# MD201x_2019-02-01.net
KiCad netlist of a schematic drawn in EAGLE
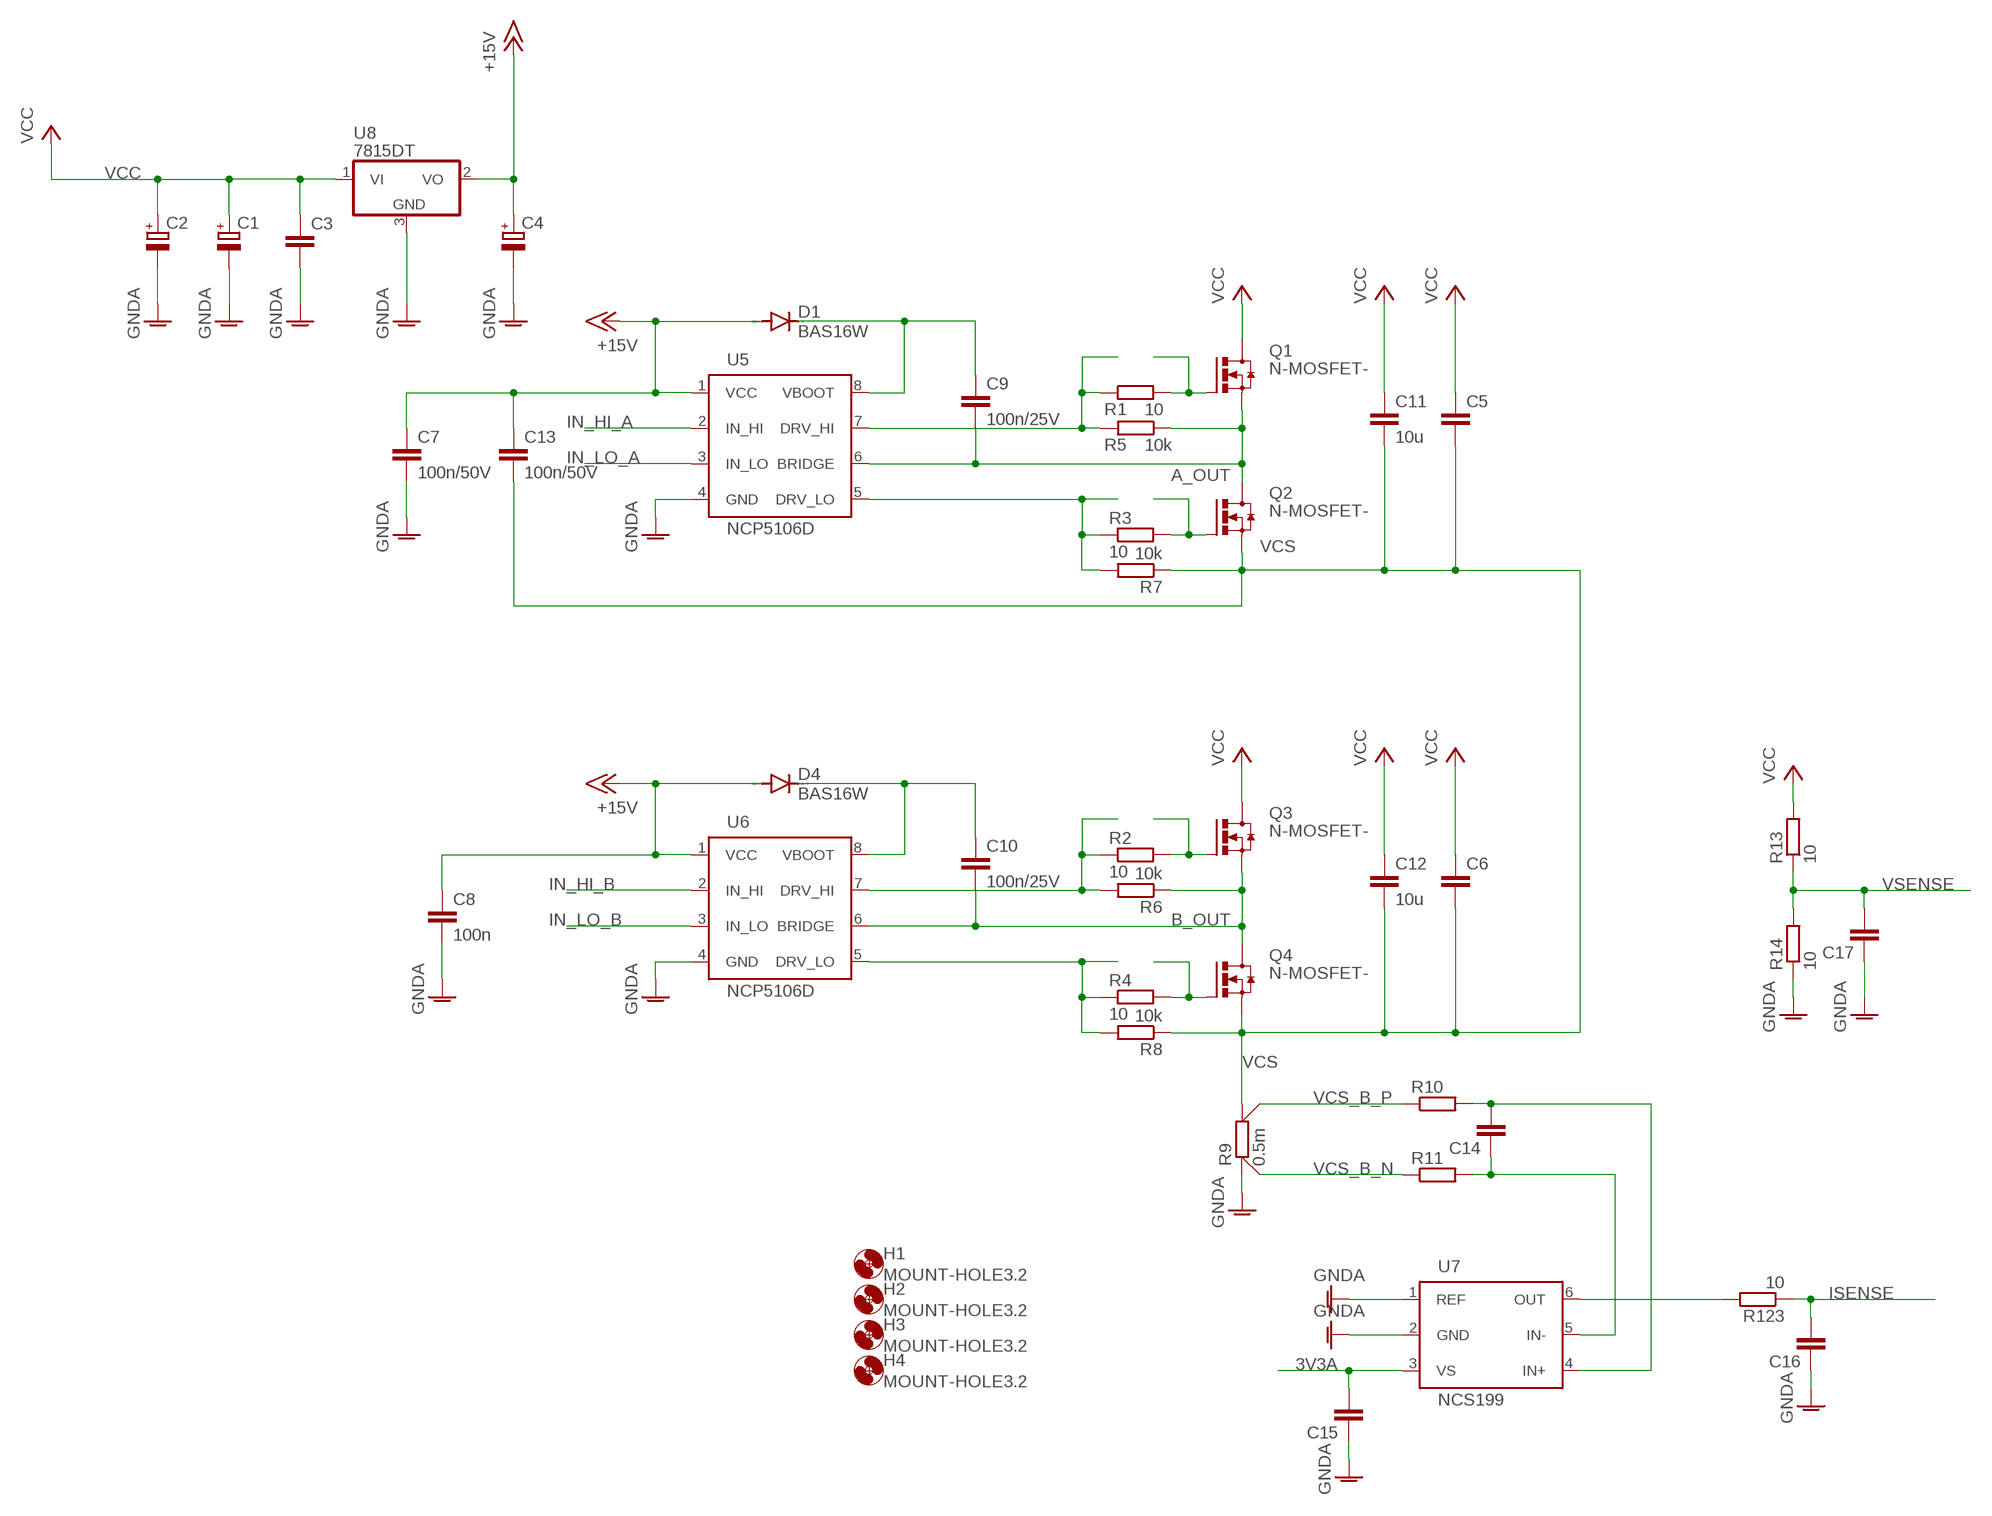
[diagram p0: schematic, sheet 1]
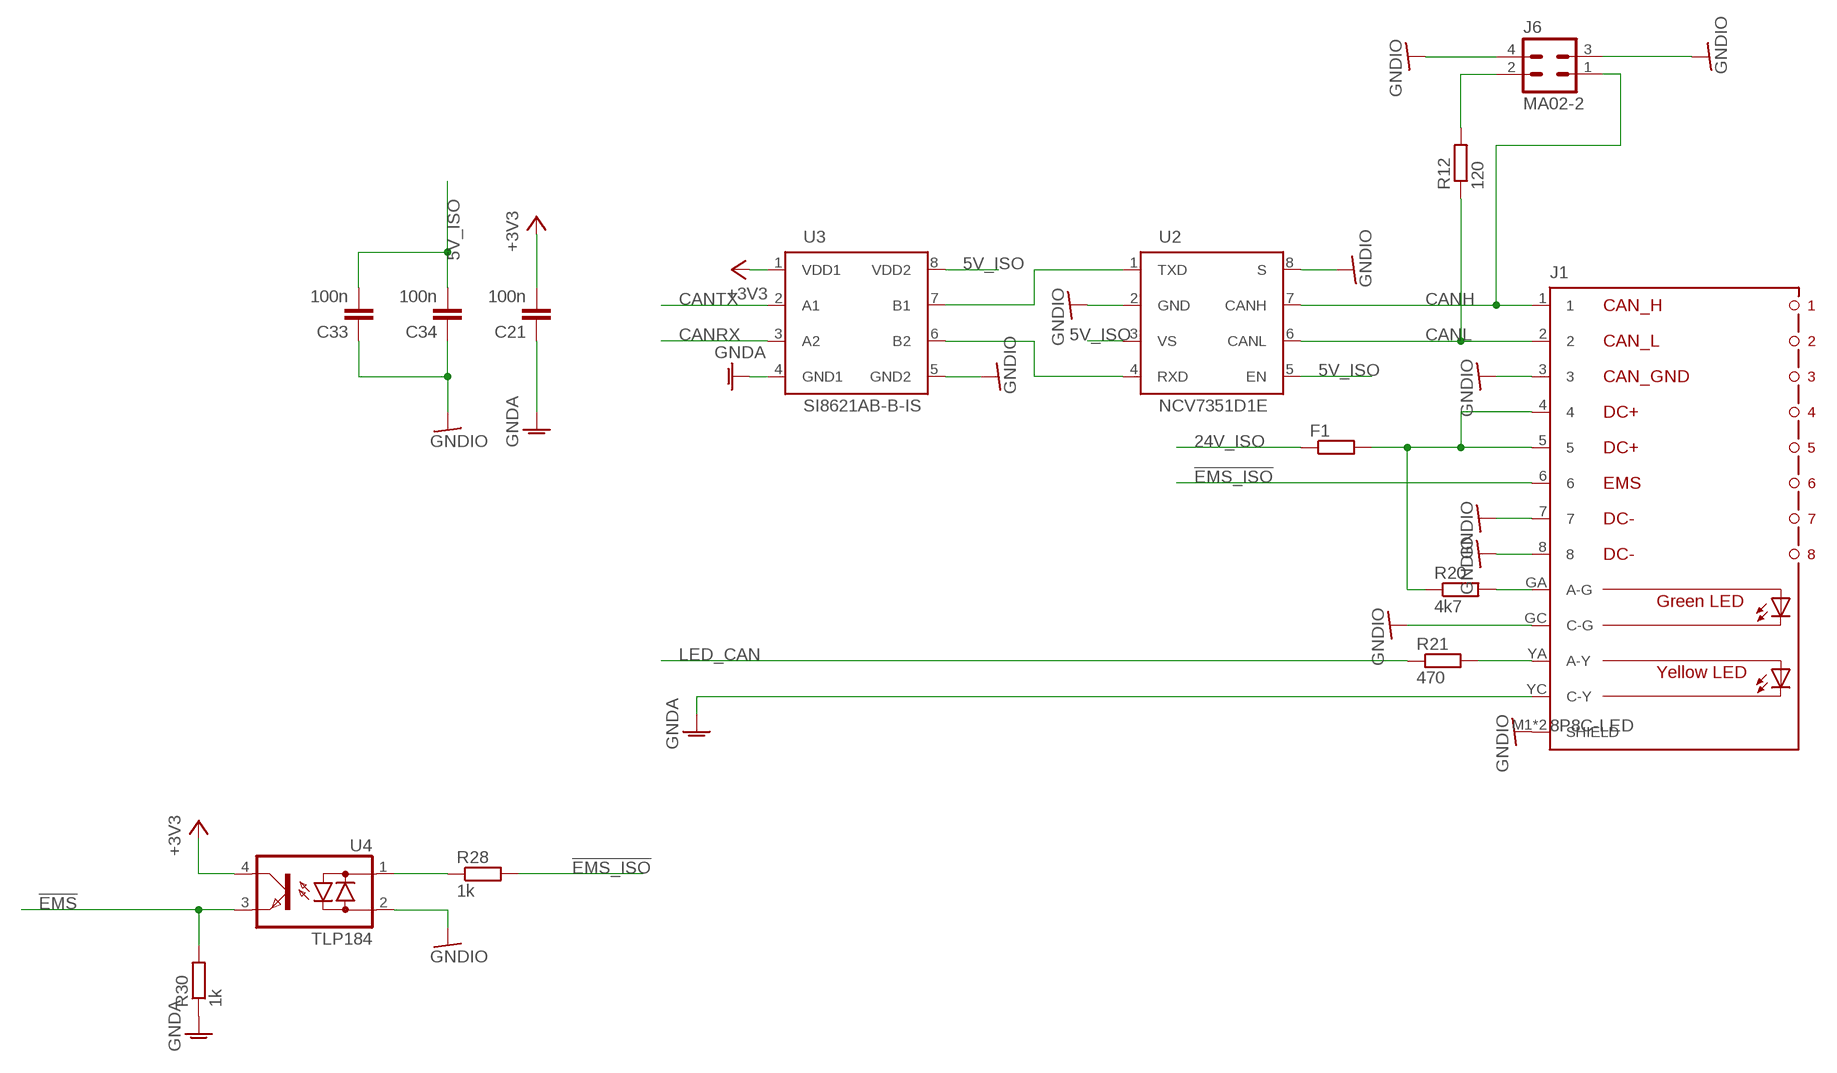
[diagram p1: schematic, sheet 2]
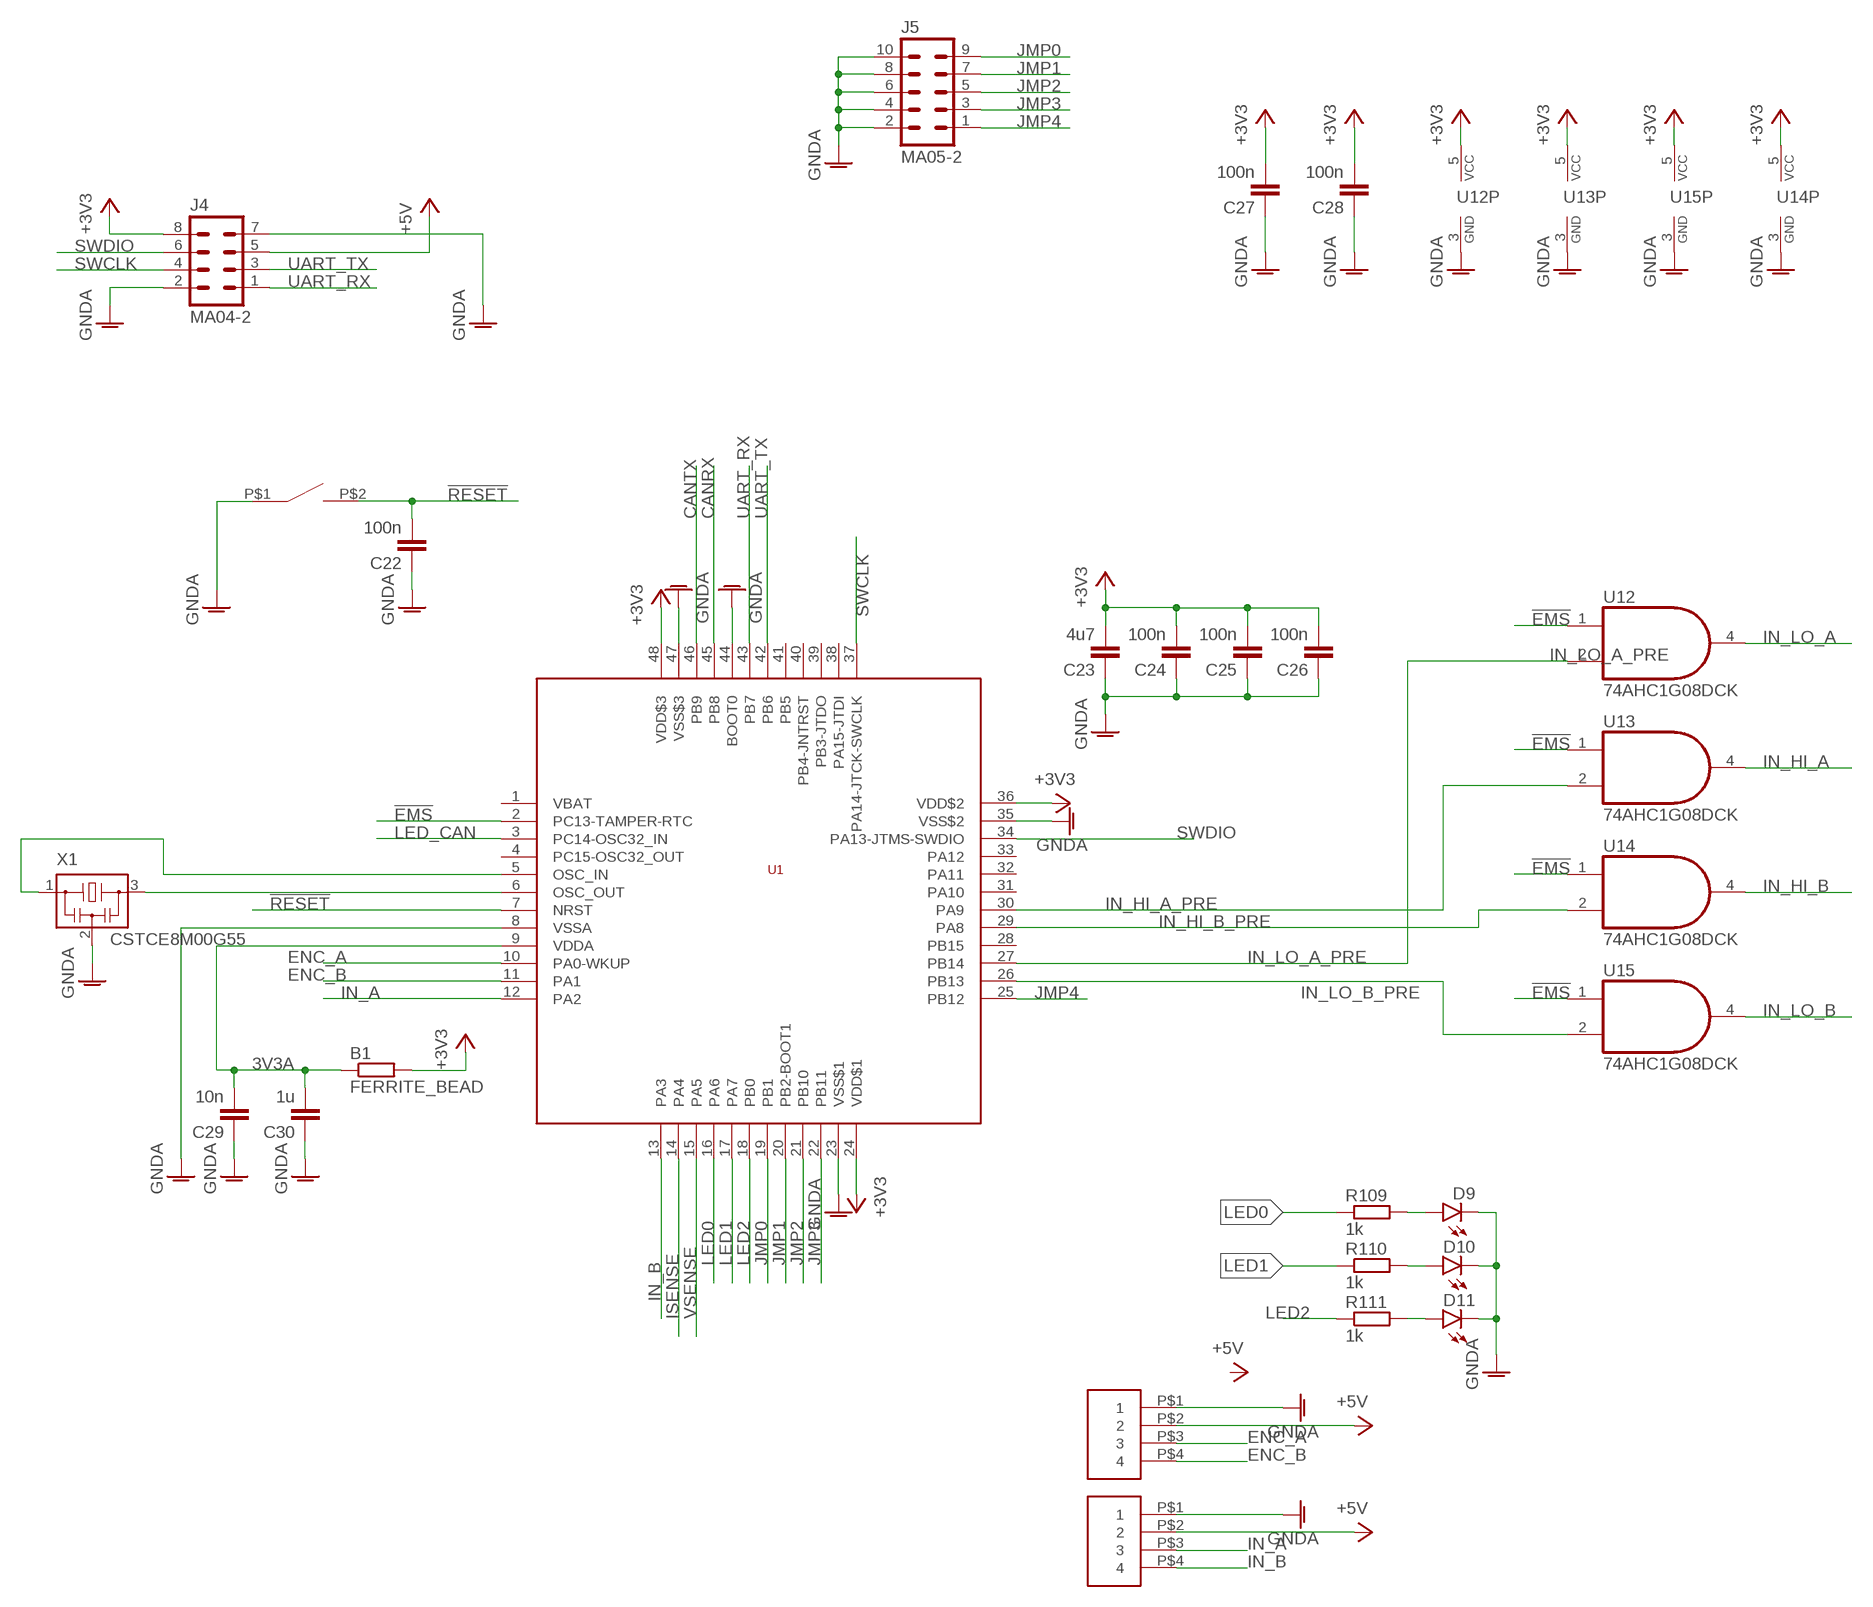
[diagram p2: schematic, sheet 3]
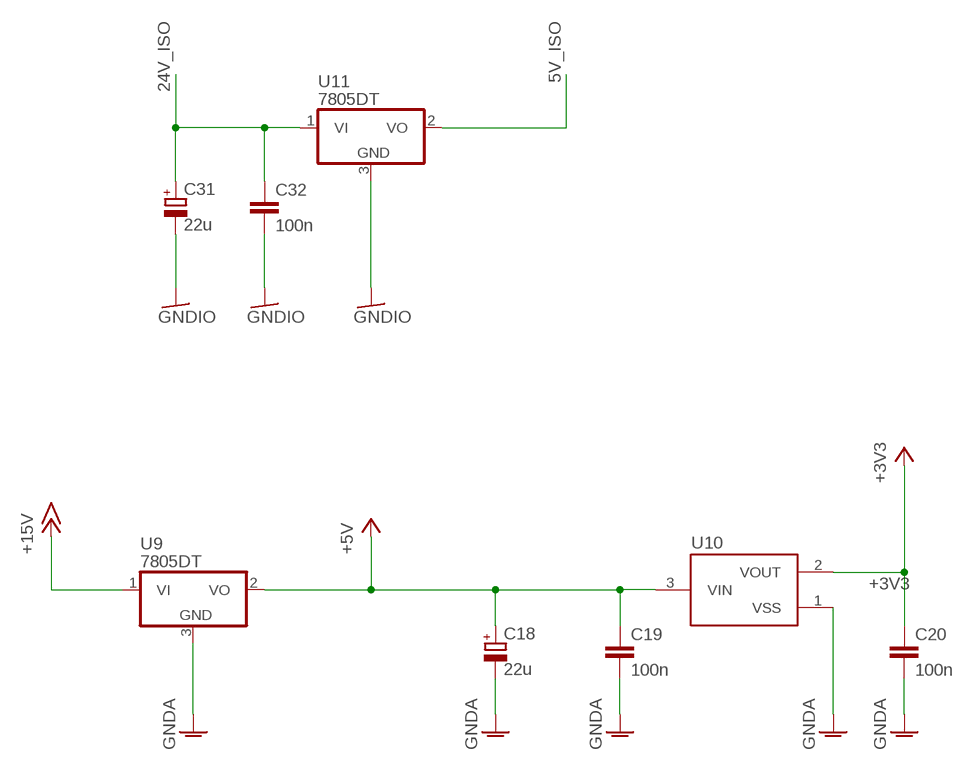
[diagram p3: schematic, sheet 4]

(export (version "E")
  (design (tool "Eeschema 10.0.6"))
  (components
    (comp (ref "C18")
      (value "22u")
      (footprint "eagle-import:E2,5-5")
      (libsource (lib "eagle-import") (part "CPOL-EUE2.5-5"))
    )
    (comp (ref "C19")
      (value "100n")
      (footprint "eagle-import:C0603")
      (libsource (lib "eagle-import") (part "C-EUC0603"))
    )
    (comp (ref "C20")
      (value "100n")
      (footprint "eagle-import:C0603")
      (libsource (lib "eagle-import") (part "C-EUC0603"))
    )
    (comp (ref "C31")
      (value "22u")
      (footprint "eagle-import:E2,5-5")
      (libsource (lib "eagle-import") (part "CPOL-EUE2.5-5"))
    )
    (comp (ref "C32")
      (value "100n")
      (footprint "eagle-import:C0603")
      (libsource (lib "eagle-import") (part "C-EUC0603"))
    )
    (comp (ref "U9")
      (value "7805DT")
      (footprint "eagle-import:TO252")
      (libsource (lib "eagle-import") (part "78DT05"))
    )
    (comp (ref "U10")
      (value "XC6206")
      (footprint "eagle-import:SOT95P240X110-3")
      (libsource (lib "eagle-import") (part "XC6206"))
    )
    (comp (ref "U11")
      (value "7805DT")
      (footprint "eagle-import:TO252")
      (libsource (lib "eagle-import") (part "78DT05"))
    )
    (comp (ref "C1")
      (value "CPOL-EUE5-10.5")
      (footprint "eagle-import:E5-10,5")
      (libsource (lib "eagle-import") (part "CPOL-EUE5-10.5"))
    )
    (comp (ref "C2")
      (value "CPOL-EUE5-10.5")
      (footprint "eagle-import:E5-10,5")
      (libsource (lib "eagle-import") (part "CPOL-EUE5-10.5"))
    )
    (comp (ref "C3")
      (value "C-EUC0603")
      (footprint "eagle-import:C0603")
      (libsource (lib "eagle-import") (part "C-EUC0603"))
    )
    (comp (ref "C4")
      (value "CPOL-EUE2.5-5")
      (footprint "eagle-import:E2,5-5")
      (libsource (lib "eagle-import") (part "CPOL-EUE2.5-5"))
    )
    (comp (ref "C5")
      (value "C-EUC0603")
      (footprint "eagle-import:C0603")
      (libsource (lib "eagle-import") (part "C-EUC0603"))
    )
    (comp (ref "C6")
      (value "C-EUC0603")
      (footprint "eagle-import:C0603")
      (libsource (lib "eagle-import") (part "C-EUC0603"))
    )
    (comp (ref "C7")
      (value "100n/50V")
      (footprint "eagle-import:C0603")
      (libsource (lib "eagle-import") (part "C-EUC0603"))
    )
    (comp (ref "C8")
      (value "100n")
      (footprint "eagle-import:C0603")
      (libsource (lib "eagle-import") (part "C-EUC0603"))
    )
    (comp (ref "C9")
      (value "100n/25V")
      (footprint "eagle-import:C0603")
      (libsource (lib "eagle-import") (part "C-EUC0603"))
    )
    (comp (ref "C10")
      (value "100n/25V")
      (footprint "eagle-import:C0603")
      (libsource (lib "eagle-import") (part "C-EUC0603"))
    )
    (comp (ref "C11")
      (value "10u")
      (footprint "eagle-import:C1210")
      (libsource (lib "eagle-import") (part "C-EUC1210"))
    )
    (comp (ref "C12")
      (value "10u")
      (footprint "eagle-import:C1210")
      (libsource (lib "eagle-import") (part "C-EUC1210"))
    )
    (comp (ref "C13")
      (value "100n/50V")
      (footprint "eagle-import:C0603")
      (libsource (lib "eagle-import") (part "C-EUC0603"))
    )
    (comp (ref "C14")
      (value "C-EUC0603")
      (footprint "eagle-import:C0603")
      (libsource (lib "eagle-import") (part "rcl_334_C-EUC0603"))
    )
    (comp (ref "C15")
      (value "C-EUC0603")
      (footprint "eagle-import:C0603")
      (libsource (lib "eagle-import") (part "rcl_334_C-EUC0603"))
    )
    (comp (ref "C16")
      (value "C-EUC0603")
      (footprint "eagle-import:C0603")
      (libsource (lib "eagle-import") (part "rcl_334_C-EUC0603"))
    )
    (comp (ref "C17")
      (value "C-EUC0603")
      (footprint "eagle-import:C0603")
      (libsource (lib "eagle-import") (part "rcl_334_C-EUC0603"))
    )
    (comp (ref "D1")
      (value "BAS16W")
      (footprint "eagle-import:SOD323-R")
      (libsource (lib "eagle-import") (part "DIODE-SOD323-R"))
    )
    (comp (ref "D4")
      (value "BAS16W")
      (footprint "eagle-import:SOD323-R")
      (libsource (lib "eagle-import") (part "DIODE-SOD323-R"))
    )
    (comp (ref "H1")
      (value "MOUNT-HOLE3.2")
      (footprint "eagle-import:3,2")
      (libsource (lib "eagle-import") (part "MOUNT-HOLE3.2"))
    )
    (comp (ref "H2")
      (value "MOUNT-HOLE3.2")
      (footprint "eagle-import:3,2")
      (libsource (lib "eagle-import") (part "MOUNT-HOLE3.2"))
    )
    (comp (ref "H3")
      (value "MOUNT-HOLE3.2")
      (footprint "eagle-import:3,2")
      (libsource (lib "eagle-import") (part "MOUNT-HOLE3.2"))
    )
    (comp (ref "H4")
      (value "MOUNT-HOLE3.2")
      (footprint "eagle-import:3,2")
      (libsource (lib "eagle-import") (part "MOUNT-HOLE3.2"))
    )
    (comp (ref "Q1")
      (value "N-MOSFET-")
      (footprint "eagle-import:SOT669")
      (libsource (lib "eagle-import") (part "N-MOSFET-"))
    )
    (comp (ref "Q2")
      (value "N-MOSFET-")
      (footprint "eagle-import:SOT669")
      (libsource (lib "eagle-import") (part "N-MOSFET-"))
    )
    (comp (ref "Q3")
      (value "N-MOSFET-")
      (footprint "eagle-import:SOT669")
      (libsource (lib "eagle-import") (part "N-MOSFET-"))
    )
    (comp (ref "Q4")
      (value "N-MOSFET-")
      (footprint "eagle-import:SOT669")
      (libsource (lib "eagle-import") (part "N-MOSFET-"))
    )
    (comp (ref "R1")
      (value "10")
      (footprint "eagle-import:R0603")
      (libsource (lib "eagle-import") (part "R-EU_R0603"))
    )
    (comp (ref "R2")
      (value "10")
      (footprint "eagle-import:R0603")
      (libsource (lib "eagle-import") (part "R-EU_R0603"))
    )
    (comp (ref "R3")
      (value "10")
      (footprint "eagle-import:R0603")
      (libsource (lib "eagle-import") (part "R-EU_R0603"))
    )
    (comp (ref "R4")
      (value "10")
      (footprint "eagle-import:R0603")
      (libsource (lib "eagle-import") (part "R-EU_R0603"))
    )
    (comp (ref "R5")
      (value "10k")
      (footprint "eagle-import:R0603")
      (libsource (lib "eagle-import") (part "R-EU_R0603"))
    )
    (comp (ref "R6")
      (value "10k")
      (footprint "eagle-import:R0603")
      (libsource (lib "eagle-import") (part "R-EU_R0603"))
    )
    (comp (ref "R7")
      (value "10k")
      (footprint "eagle-import:R0603")
      (libsource (lib "eagle-import") (part "R-EU_R0603"))
    )
    (comp (ref "R8")
      (value "10k")
      (footprint "eagle-import:R0603")
      (libsource (lib "eagle-import") (part "R-EU_R0603"))
    )
    (comp (ref "R9")
      (value "0.5m")
      (footprint "eagle-import:CSS2H-2512")
      (libsource (lib "eagle-import") (part "CSS2H-2512"))
    )
    (comp (ref "R10")
      (value "R-EU_R0603")
      (footprint "eagle-import:R0603")
      (libsource (lib "eagle-import") (part "rcl_334_R-EU_R0603"))
    )
    (comp (ref "R11")
      (value "R-EU_R0603")
      (footprint "eagle-import:R0603")
      (libsource (lib "eagle-import") (part "rcl_334_R-EU_R0603"))
    )
    (comp (ref "R13")
      (value "10")
      (footprint "eagle-import:R0603")
      (libsource (lib "eagle-import") (part "R-EU_R0603"))
    )
    (comp (ref "R14")
      (value "10")
      (footprint "eagle-import:R0603")
      (libsource (lib "eagle-import") (part "R-EU_R0603"))
    )
    (comp (ref "R123")
      (value "10")
      (footprint "eagle-import:R0603")
      (libsource (lib "eagle-import") (part "R-EU_R0603"))
    )
    (comp (ref "U5")
      (value "NCP5106D")
      (footprint "eagle-import:SOIC127P600X175-8")
      (libsource (lib "eagle-import") (part "NCP5106D"))
    )
    (comp (ref "U6")
      (value "NCP5106D")
      (footprint "eagle-import:SOIC127P600X175-8")
      (libsource (lib "eagle-import") (part "NCP5106D"))
    )
    (comp (ref "U7")
      (value "NCS199")
      (footprint "eagle-import:SOT65P210X110-6")
      (libsource (lib "eagle-import") (part "NCS199"))
    )
    (comp (ref "U8")
      (value "7815DT")
      (footprint "eagle-import:TO252")
      (libsource (lib "eagle-import") (part "78DT15"))
    )
    (comp (ref "B1")
      (value "FERRITE_BEAD")
      (footprint "eagle-import:R0603")
      (libsource (lib "eagle-import") (part "R-EU_R0603"))
    )
    (comp (ref "C22")
      (value "100n")
      (footprint "eagle-import:C0603")
      (libsource (lib "eagle-import") (part "C-EUC0603"))
    )
    (comp (ref "C23")
      (value "4u7")
      (footprint "eagle-import:C0805")
      (libsource (lib "eagle-import") (part "C-EUC0805"))
    )
    (comp (ref "C24")
      (value "100n")
      (footprint "eagle-import:C0603")
      (libsource (lib "eagle-import") (part "C-EUC0603"))
    )
    (comp (ref "C25")
      (value "100n")
      (footprint "eagle-import:C0603")
      (libsource (lib "eagle-import") (part "C-EUC0603"))
    )
    (comp (ref "C26")
      (value "100n")
      (footprint "eagle-import:C0603")
      (libsource (lib "eagle-import") (part "C-EUC0603"))
    )
    (comp (ref "C27")
      (value "100n")
      (footprint "eagle-import:C0603")
      (libsource (lib "eagle-import") (part "C-EUC0603"))
    )
    (comp (ref "C28")
      (value "100n")
      (footprint "eagle-import:C0603")
      (libsource (lib "eagle-import") (part "C-EUC0603"))
    )
    (comp (ref "C29")
      (value "10n")
      (footprint "eagle-import:C0603")
      (libsource (lib "eagle-import") (part "C-EUC0603"))
    )
    (comp (ref "C30")
      (value "1u")
      (footprint "eagle-import:C0603")
      (libsource (lib "eagle-import") (part "C-EUC0603"))
    )
    (comp (ref "D9")
      (value "LEDCHIPLED_0805")
      (footprint "eagle-import:CHIPLED_0805")
      (libsource (lib "eagle-import") (part "LEDCHIPLED_0805"))
    )
    (comp (ref "D10")
      (value "LEDCHIPLED_0805")
      (footprint "eagle-import:CHIPLED_0805")
      (libsource (lib "eagle-import") (part "LEDCHIPLED_0805"))
    )
    (comp (ref "D11")
      (value "LEDCHIPLED_0805")
      (footprint "eagle-import:CHIPLED_0805")
      (libsource (lib "eagle-import") (part "LEDCHIPLED_0805"))
    )
    (comp (ref "J2")
      (value "XH-4-SIDE")
      (footprint "eagle-import:CON-XH-4-SIDE")
      (libsource (lib "eagle-import") (part "XH-4-SIDE"))
    )
    (comp (ref "J3")
      (value "XH-4-SIDE")
      (footprint "eagle-import:CON-XH-4-SIDE")
      (libsource (lib "eagle-import") (part "XH-4-SIDE"))
    )
    (comp (ref "J4")
      (value "MA04-2")
      (footprint "eagle-import:MA04-2W")
      (libsource (lib "eagle-import") (part "MA04-2"))
    )
    (comp (ref "J5")
      (value "MA05-2")
      (footprint "eagle-import:MA05-2W")
      (libsource (lib "eagle-import") (part "MA05-2"))
    )
    (comp (ref "R109")
      (value "1k")
      (footprint "eagle-import:R0603")
      (libsource (lib "eagle-import") (part "R-EU_R0603"))
    )
    (comp (ref "R110")
      (value "1k")
      (footprint "eagle-import:R0603")
      (libsource (lib "eagle-import") (part "R-EU_R0603"))
    )
    (comp (ref "R111")
      (value "1k")
      (footprint "eagle-import:R0603")
      (libsource (lib "eagle-import") (part "R-EU_R0603"))
    )
    (comp (ref "S1")
      (value "SWITCH_TACTILETOP")
      (footprint "eagle-import:SWITCH_TACTILE_3X6")
      (libsource (lib "eagle-import") (part "SWITCH_TACTILETOP"))
    )
    (comp (ref "U1")
      (value "STM32F103C8")
      (footprint "eagle-import:LQFP48")
      (libsource (lib "eagle-import") (part "STM32F103C8"))
    )
    (comp (ref "U12")
      (value "74AHC1G08DCK")
      (footprint "eagle-import:SC70-5")
      (libsource (lib "eagle-import") (part "741G08DCKAHC"))
    )
    (comp (ref "U13")
      (value "74AHC1G08DCK")
      (footprint "eagle-import:SC70-5")
      (libsource (lib "eagle-import") (part "741G08DCKAHC"))
    )
    (comp (ref "U14")
      (value "74AHC1G08DCK")
      (footprint "eagle-import:SC70-5")
      (libsource (lib "eagle-import") (part "741G08DCKAHC"))
    )
    (comp (ref "U15")
      (value "74AHC1G08DCK")
      (footprint "eagle-import:SC70-5")
      (libsource (lib "eagle-import") (part "741G08DCKAHC"))
    )
    (comp (ref "X1")
      (value "CSTCE8M00G55")
      (footprint "eagle-import:CSTCE8M00G55")
      (libsource (lib "eagle-import") (part "CSTCE8M00G55"))
    )
    (comp (ref "C21")
      (value "100n")
      (footprint "eagle-import:C0603")
      (libsource (lib "eagle-import") (part "C-EUC0603"))
    )
    (comp (ref "C33")
      (value "100n")
      (footprint "eagle-import:C0805")
      (libsource (lib "eagle-import") (part "C-EUC0805"))
    )
    (comp (ref "C34")
      (value "100n")
      (footprint "eagle-import:C0603")
      (libsource (lib "eagle-import") (part "C-EUC0603"))
    )
    (comp (ref "F1")
      (value "R-EU_R1206")
      (footprint "eagle-import:R1206")
      (libsource (lib "eagle-import") (part "rcl_334_R-EU_R1206"))
    )
    (comp (ref "J1")
      (value "8P8C-LED")
      (footprint "eagle-import:8P8C-LED")
      (libsource (lib "eagle-import") (part "8P8C-LED"))
    )
    (comp (ref "J6")
      (value "MA02-2")
      (footprint "eagle-import:MA02-2W")
      (libsource (lib "eagle-import") (part "MA02-2"))
    )
    (comp (ref "R12")
      (value "120")
      (footprint "eagle-import:R0603")
      (libsource (lib "eagle-import") (part "rcl_334_R-EU_R0603"))
    )
    (comp (ref "R20")
      (value "4k7")
      (footprint "eagle-import:R0603")
      (libsource (lib "eagle-import") (part "rcl_334_R-EU_R0603"))
    )
    (comp (ref "R21")
      (value "470")
      (footprint "eagle-import:R0603")
      (libsource (lib "eagle-import") (part "rcl_334_R-EU_R0603"))
    )
    (comp (ref "R28")
      (value "1k")
      (footprint "eagle-import:R0603")
      (libsource (lib "eagle-import") (part "rcl_334_R-EU_R0603"))
    )
    (comp (ref "R30")
      (value "1k")
      (footprint "eagle-import:R0603")
      (libsource (lib "eagle-import") (part "rcl_334_R-EU_R0603"))
    )
    (comp (ref "U2")
      (value "NCV7351D1E")
      (footprint "eagle-import:SO08")
      (libsource (lib "eagle-import") (part "NCV7351D1E"))
    )
    (comp (ref "U3")
      (value "SI8621AB-B-IS")
      (footprint "eagle-import:SO08")
      (libsource (lib "eagle-import") (part "SI8621AB-B-IS"))
    )
    (comp (ref "U4")
      (value "TLP184")
      (footprint "eagle-import:11-4M1S")
      (libsource (lib "eagle-import") (part "TLP184"))
    )
  )
  (nets
    (net (code "1") (name "+3V3") (class "Default")
      (node (ref "B1") (pin "2") (pinfunction "2_2") (pintype "passive"))
      (node (ref "C20") (pin "1") (pinfunction "1_1") (pintype "passive"))
      (node (ref "C21") (pin "2") (pinfunction "2_2") (pintype "passive"))
      (node (ref "C23") (pin "2") (pinfunction "2_2") (pintype "passive"))
      (node (ref "C24") (pin "2") (pinfunction "2_2") (pintype "passive"))
      (node (ref "C25") (pin "2") (pinfunction "2_2") (pintype "passive"))
      (node (ref "C26") (pin "2") (pinfunction "2_2") (pintype "passive"))
      (node (ref "C27") (pin "2") (pinfunction "2_2") (pintype "passive"))
      (node (ref "C28") (pin "2") (pinfunction "2_2") (pintype "passive"))
      (node (ref "J4") (pin "8") (pinfunction "8_8") (pintype "passive"))
      (node (ref "U1") (pin "24") (pinfunction "VDD$1_24") (pintype "passive"))
      (node (ref "U1") (pin "36") (pinfunction "VDD$2_36") (pintype "passive"))
      (node (ref "U1") (pin "48") (pinfunction "VDD$3_48") (pintype "passive"))
      (node (ref "U10") (pin "2") (pinfunction "VOUT_2") (pintype "bidirectional"))
      (node (ref "U12") (pin "5") (pinfunction "VCC_5") (pintype "power_in"))
      (node (ref "U13") (pin "5") (pinfunction "VCC_5") (pintype "power_in"))
      (node (ref "U14") (pin "5") (pinfunction "VCC_5") (pintype "power_in"))
      (node (ref "U15") (pin "5") (pinfunction "VCC_5") (pintype "power_in"))
      (node (ref "U3") (pin "1") (pinfunction "VDD1_1") (pintype "power_in"))
      (node (ref "U4") (pin "4") (pinfunction "C_4") (pintype "passive"))
    )
    (net (code "2") (name "+5V") (class "Default")
      (node (ref "C18") (pin "+") (pinfunction "+_+") (pintype "passive"))
      (node (ref "C19") (pin "1") (pinfunction "1_1") (pintype "passive"))
      (node (ref "J2") (pin "P$2") (pinfunction "2_P$2") (pintype "bidirectional"))
      (node (ref "J3") (pin "P$2") (pinfunction "2_P$2") (pintype "bidirectional"))
      (node (ref "J4") (pin "5") (pinfunction "5_5") (pintype "passive"))
      (node (ref "U10") (pin "3") (pinfunction "VIN_3") (pintype "bidirectional"))
      (node (ref "U9") (pin "2") (pinfunction "VO_2") (pintype "passive"))
    )
    (net (code "3") (name "+15V") (class "Default")
      (node (ref "C13") (pin "1") (pinfunction "1_1") (pintype "passive"))
      (node (ref "C4") (pin "+") (pinfunction "+_+") (pintype "passive"))
      (node (ref "C7") (pin "1") (pinfunction "1_1") (pintype "passive"))
      (node (ref "C8") (pin "1") (pinfunction "1_1") (pintype "passive"))
      (node (ref "D1") (pin "A") (pinfunction "A_A") (pintype "passive"))
      (node (ref "D4") (pin "A") (pinfunction "A_A") (pintype "passive"))
      (node (ref "U5") (pin "1") (pinfunction "VCC_1") (pintype "power_in"))
      (node (ref "U6") (pin "1") (pinfunction "VCC_1") (pintype "power_in"))
      (node (ref "U8") (pin "2") (pinfunction "VO_2") (pintype "passive"))
      (node (ref "U9") (pin "1") (pinfunction "VI_1") (pintype "input"))
    )
    (net (code "4") (name "3V3A") (class "Default")
      (node (ref "B1") (pin "1") (pinfunction "1_1") (pintype "passive"))
      (node (ref "C15") (pin "2") (pinfunction "2_2") (pintype "passive"))
      (node (ref "C29") (pin "2") (pinfunction "2_2") (pintype "passive"))
      (node (ref "C30") (pin "2") (pinfunction "2_2") (pintype "passive"))
      (node (ref "U1") (pin "9") (pinfunction "VDDA_9") (pintype "bidirectional"))
      (node (ref "U7") (pin "3") (pinfunction "VS_3") (pintype "power_in"))
    )
    (net (code "5") (name "5V_ISO") (class "Default")
      (node (ref "C33") (pin "2") (pinfunction "2_2") (pintype "passive"))
      (node (ref "C34") (pin "2") (pinfunction "2_2") (pintype "passive"))
      (node (ref "U11") (pin "2") (pinfunction "VO_2") (pintype "passive"))
      (node (ref "U2") (pin "3") (pinfunction "VS_3") (pintype "power_in"))
      (node (ref "U2") (pin "5") (pinfunction "EN_5") (pintype "input"))
      (node (ref "U3") (pin "8") (pinfunction "VDD2_8") (pintype "power_in"))
    )
    (net (code "6") (name "24V_ISO") (class "Default")
      (node (ref "C31") (pin "+") (pinfunction "+_+") (pintype "passive"))
      (node (ref "C32") (pin "1") (pinfunction "1_1") (pintype "passive"))
      (node (ref "F1") (pin "1") (pinfunction "1_1") (pintype "passive"))
      (node (ref "U11") (pin "1") (pinfunction "VI_1") (pintype "input"))
    )
    (net (code "7") (name "A_OUT") (class "Default")
      (node (ref "C9") (pin "2") (pinfunction "2_2") (pintype "passive"))
      (node (ref "Q1") (pin "1") (pinfunction "SOURCE_1") (pintype "passive"))
      (node (ref "Q1") (pin "2") (pinfunction "SOURCE_2") (pintype "passive"))
      (node (ref "Q1") (pin "3") (pinfunction "SOURCE_3") (pintype "passive"))
      (node (ref "Q2") (pin "5") (pinfunction "DRAIN_5") (pintype "passive"))
      (node (ref "R5") (pin "1") (pinfunction "1_1") (pintype "passive"))
      (node (ref "U5") (pin "6") (pinfunction "BRIDGE_6") (pintype "power_in"))
    )
    (net (code "8") (name "B_OUT") (class "Default")
      (node (ref "C10") (pin "2") (pinfunction "2_2") (pintype "passive"))
      (node (ref "Q3") (pin "1") (pinfunction "SOURCE_1") (pintype "passive"))
      (node (ref "Q3") (pin "2") (pinfunction "SOURCE_2") (pintype "passive"))
      (node (ref "Q3") (pin "3") (pinfunction "SOURCE_3") (pintype "passive"))
      (node (ref "Q4") (pin "5") (pinfunction "DRAIN_5") (pintype "passive"))
      (node (ref "R6") (pin "1") (pinfunction "1_1") (pintype "passive"))
      (node (ref "U6") (pin "6") (pinfunction "BRIDGE_6") (pintype "power_in"))
    )
    (net (code "9") (name "CANH") (class "Default")
      (node (ref "J1") (pin "1") (pinfunction "1_1") (pintype "input"))
      (node (ref "J6") (pin "1") (pinfunction "1_1") (pintype "passive"))
      (node (ref "U2") (pin "7") (pinfunction "CANH_7") (pintype "output"))
    )
    (net (code "10") (name "CANL") (class "Default")
      (node (ref "J1") (pin "2") (pinfunction "2_2") (pintype "input"))
      (node (ref "R12") (pin "1") (pinfunction "1_1") (pintype "passive"))
      (node (ref "U2") (pin "6") (pinfunction "CANL_6") (pintype "output"))
    )
    (net (code "11") (name "CANRX") (class "Default")
      (node (ref "U1") (pin "45") (pinfunction "PB8_45") (pintype "bidirectional"))
      (node (ref "U3") (pin "3") (pinfunction "A2_3") (pintype "output"))
    )
    (net (code "12") (name "CANTX") (class "Default")
      (node (ref "U1") (pin "46") (pinfunction "PB9_46") (pintype "bidirectional"))
      (node (ref "U3") (pin "2") (pinfunction "A1_2") (pintype "input"))
    )
    (net (code "13") (name "ENC_A") (class "Default")
      (node (ref "J2") (pin "P$3") (pinfunction "3_P$3") (pintype "bidirectional"))
      (node (ref "U1") (pin "10") (pinfunction "PA0-WKUP_10") (pintype "bidirectional"))
    )
    (net (code "14") (name "ENC_B") (class "Default")
      (node (ref "J2") (pin "P$4") (pinfunction "4_P$4") (pintype "bidirectional"))
      (node (ref "U1") (pin "11") (pinfunction "PA1_11") (pintype "bidirectional"))
    )
    (net (code "15") (name "GNDA") (class "Default")
      (node (ref "C1") (pin "-") (pinfunction "-_-") (pintype "passive"))
      (node (ref "C15") (pin "1") (pinfunction "1_1") (pintype "passive"))
      (node (ref "C16") (pin "1") (pinfunction "1_1") (pintype "passive"))
      (node (ref "C17") (pin "1") (pinfunction "1_1") (pintype "passive"))
      (node (ref "C18") (pin "-") (pinfunction "-_-") (pintype "passive"))
      (node (ref "C19") (pin "2") (pinfunction "2_2") (pintype "passive"))
      (node (ref "C2") (pin "-") (pinfunction "-_-") (pintype "passive"))
      (node (ref "C20") (pin "2") (pinfunction "2_2") (pintype "passive"))
      (node (ref "C21") (pin "1") (pinfunction "1_1") (pintype "passive"))
      (node (ref "C22") (pin "1") (pinfunction "1_1") (pintype "passive"))
      (node (ref "C23") (pin "1") (pinfunction "1_1") (pintype "passive"))
      (node (ref "C24") (pin "1") (pinfunction "1_1") (pintype "passive"))
      (node (ref "C25") (pin "1") (pinfunction "1_1") (pintype "passive"))
      (node (ref "C26") (pin "1") (pinfunction "1_1") (pintype "passive"))
      (node (ref "C27") (pin "1") (pinfunction "1_1") (pintype "passive"))
      (node (ref "C28") (pin "1") (pinfunction "1_1") (pintype "passive"))
      (node (ref "C29") (pin "1") (pinfunction "1_1") (pintype "passive"))
      (node (ref "C3") (pin "2") (pinfunction "2_2") (pintype "passive"))
      (node (ref "C30") (pin "1") (pinfunction "1_1") (pintype "passive"))
      (node (ref "C4") (pin "-") (pinfunction "-_-") (pintype "passive"))
      (node (ref "C7") (pin "2") (pinfunction "2_2") (pintype "passive"))
      (node (ref "C8") (pin "2") (pinfunction "2_2") (pintype "passive"))
      (node (ref "D10") (pin "C") (pinfunction "C_C") (pintype "passive"))
      (node (ref "D11") (pin "C") (pinfunction "C_C") (pintype "passive"))
      (node (ref "D9") (pin "C") (pinfunction "C_C") (pintype "passive"))
      (node (ref "J1") (pin "YC") (pinfunction "C-Y_YC") (pintype "passive"))
      (node (ref "J2") (pin "P$1") (pinfunction "1_P$1") (pintype "bidirectional"))
      (node (ref "J3") (pin "P$1") (pinfunction "1_P$1") (pintype "bidirectional"))
      (node (ref "J4") (pin "2") (pinfunction "2_2") (pintype "passive"))
      (node (ref "J4") (pin "7") (pinfunction "7_7") (pintype "passive"))
      (node (ref "J5") (pin "10") (pinfunction "10_10") (pintype "passive"))
      (node (ref "J5") (pin "2") (pinfunction "2_2") (pintype "passive"))
      (node (ref "J5") (pin "4") (pinfunction "4_4") (pintype "passive"))
      (node (ref "J5") (pin "6") (pinfunction "6_6") (pintype "passive"))
      (node (ref "J5") (pin "8") (pinfunction "8_8") (pintype "passive"))
      (node (ref "R14") (pin "1") (pinfunction "1_1") (pintype "passive"))
      (node (ref "R30") (pin "1") (pinfunction "1_1") (pintype "passive"))
      (node (ref "R9") (pin "1$1") (pinfunction "1_1$1") (pintype "passive"))
      (node (ref "R9") (pin "1$2") (pinfunction "1_1$2") (pintype "passive"))
      (node (ref "S1") (pin "P$1") (pinfunction "1_P$1") (pintype "bidirectional"))
      (node (ref "U1") (pin "23") (pinfunction "VSS$1_23") (pintype "passive"))
      (node (ref "U1") (pin "35") (pinfunction "VSS$2_35") (pintype "passive"))
      (node (ref "U1") (pin "44") (pinfunction "BOOT0_44") (pintype "input"))
      (node (ref "U1") (pin "47") (pinfunction "VSS$3_47") (pintype "passive"))
      (node (ref "U1") (pin "8") (pinfunction "VSSA_8") (pintype "bidirectional"))
      (node (ref "U10") (pin "1") (pinfunction "VSS_1") (pintype "bidirectional"))
      (node (ref "U12") (pin "3") (pinfunction "GND_3") (pintype "power_in"))
      (node (ref "U13") (pin "3") (pinfunction "GND_3") (pintype "power_in"))
      (node (ref "U14") (pin "3") (pinfunction "GND_3") (pintype "power_in"))
      (node (ref "U15") (pin "3") (pinfunction "GND_3") (pintype "power_in"))
      (node (ref "U3") (pin "4") (pinfunction "GND1_4") (pintype "power_in"))
      (node (ref "U5") (pin "4") (pinfunction "GND_4") (pintype "power_in"))
      (node (ref "U6") (pin "4") (pinfunction "GND_4") (pintype "power_in"))
      (node (ref "U7") (pin "1") (pinfunction "REF_1") (pintype "power_in"))
      (node (ref "U7") (pin "2") (pinfunction "GND_2") (pintype "power_in"))
      (node (ref "U8") (pin "3") (pinfunction "GND_3") (pintype "passive"))
      (node (ref "U9") (pin "3") (pinfunction "GND_3") (pintype "passive"))
      (node (ref "X1") (pin "2") (pinfunction "2_2") (pintype "passive"))
    )
    (net (code "16") (name "GNDIO") (class "Default")
      (node (ref "C31") (pin "-") (pinfunction "-_-") (pintype "passive"))
      (node (ref "C32") (pin "2") (pinfunction "2_2") (pintype "passive"))
      (node (ref "C33") (pin "1") (pinfunction "1_1") (pintype "passive"))
      (node (ref "C34") (pin "1") (pinfunction "1_1") (pintype "passive"))
      (node (ref "J1") (pin "3") (pinfunction "3_3") (pintype "input"))
      (node (ref "J1") (pin "7") (pinfunction "7_7") (pintype "input"))
      (node (ref "J1") (pin "8") (pinfunction "8_8") (pintype "input"))
      (node (ref "J1") (pin "GC") (pinfunction "C-G_GC") (pintype "passive"))
      (node (ref "J1") (pin "M1") (pinfunction "SHIELD_M1") (pintype "passive"))
      (node (ref "J1") (pin "M2") (pinfunction "SHIELD_M2") (pintype "passive"))
      (node (ref "J6") (pin "3") (pinfunction "3_3") (pintype "passive"))
      (node (ref "J6") (pin "4") (pinfunction "4_4") (pintype "passive"))
      (node (ref "U11") (pin "3") (pinfunction "GND_3") (pintype "passive"))
      (node (ref "U2") (pin "2") (pinfunction "GND_2") (pintype "power_in"))
      (node (ref "U2") (pin "8") (pinfunction "S_8") (pintype "input"))
      (node (ref "U3") (pin "5") (pinfunction "GND2_5") (pintype "power_in"))
      (node (ref "U4") (pin "2") (pinfunction "AC2_2") (pintype "passive"))
    )
    (net (code "17") (name "IN_A") (class "Default")
      (node (ref "J3") (pin "P$3") (pinfunction "3_P$3") (pintype "bidirectional"))
      (node (ref "U1") (pin "12") (pinfunction "PA2_12") (pintype "bidirectional"))
    )
    (net (code "18") (name "IN_B") (class "Default")
      (node (ref "J3") (pin "P$4") (pinfunction "4_P$4") (pintype "bidirectional"))
      (node (ref "U1") (pin "13") (pinfunction "PA3_13") (pintype "bidirectional"))
    )
    (net (code "19") (name "IN_HI_A") (class "Default")
      (node (ref "U13") (pin "4") (pinfunction "O_4") (pintype "output"))
      (node (ref "U5") (pin "2") (pinfunction "IN_HI_2") (pintype "input"))
    )
    (net (code "20") (name "IN_HI_A_PRE") (class "Default")
      (node (ref "U1") (pin "30") (pinfunction "PA9_30") (pintype "bidirectional"))
      (node (ref "U13") (pin "2") (pinfunction "I1_2") (pintype "input"))
    )
    (net (code "21") (name "IN_HI_B") (class "Default")
      (node (ref "U14") (pin "4") (pinfunction "O_4") (pintype "output"))
      (node (ref "U6") (pin "2") (pinfunction "IN_HI_2") (pintype "input"))
    )
    (net (code "22") (name "IN_HI_B_PRE") (class "Default")
      (node (ref "U1") (pin "29") (pinfunction "PA8_29") (pintype "bidirectional"))
      (node (ref "U14") (pin "2") (pinfunction "I1_2") (pintype "input"))
    )
    (net (code "23") (name "IN_LO_A") (class "Default")
      (node (ref "U12") (pin "4") (pinfunction "O_4") (pintype "output"))
      (node (ref "U5") (pin "3") (pinfunction "IN_LO_3") (pintype "input"))
    )
    (net (code "24") (name "IN_LO_A_PRE") (class "Default")
      (node (ref "U1") (pin "27") (pinfunction "PB14_27") (pintype "bidirectional"))
      (node (ref "U12") (pin "2") (pinfunction "I1_2") (pintype "input"))
    )
    (net (code "25") (name "IN_LO_B") (class "Default")
      (node (ref "U15") (pin "4") (pinfunction "O_4") (pintype "output"))
      (node (ref "U6") (pin "3") (pinfunction "IN_LO_3") (pintype "input"))
    )
    (net (code "26") (name "IN_LO_B_PRE") (class "Default")
      (node (ref "U1") (pin "26") (pinfunction "PB13_26") (pintype "bidirectional"))
      (node (ref "U15") (pin "2") (pinfunction "I1_2") (pintype "input"))
    )
    (net (code "27") (name "ISENSE") (class "Default")
      (node (ref "C16") (pin "2") (pinfunction "2_2") (pintype "passive"))
      (node (ref "R123") (pin "1") (pinfunction "1_1") (pintype "passive"))
      (node (ref "U1") (pin "14") (pinfunction "PA4_14") (pintype "bidirectional"))
    )
    (net (code "28") (name "JMP0") (class "Default")
      (node (ref "J5") (pin "9") (pinfunction "9_9") (pintype "passive"))
      (node (ref "U1") (pin "19") (pinfunction "PB1_19") (pintype "bidirectional"))
    )
    (net (code "29") (name "JMP1") (class "Default")
      (node (ref "J5") (pin "7") (pinfunction "7_7") (pintype "passive"))
      (node (ref "U1") (pin "20") (pinfunction "PB2-BOOT1_20") (pintype "bidirectional"))
    )
    (net (code "30") (name "JMP2") (class "Default")
      (node (ref "J5") (pin "5") (pinfunction "5_5") (pintype "passive"))
      (node (ref "U1") (pin "21") (pinfunction "PB10_21") (pintype "bidirectional"))
    )
    (net (code "31") (name "JMP3") (class "Default")
      (node (ref "J5") (pin "3") (pinfunction "3_3") (pintype "passive"))
      (node (ref "U1") (pin "22") (pinfunction "PB11_22") (pintype "bidirectional"))
    )
    (net (code "32") (name "JMP4") (class "Default")
      (node (ref "J5") (pin "1") (pinfunction "1_1") (pintype "passive"))
      (node (ref "U1") (pin "25") (pinfunction "PB12_25") (pintype "bidirectional"))
    )
    (net (code "33") (name "LED0") (class "Default")
      (node (ref "R109") (pin "1") (pinfunction "1_1") (pintype "passive"))
      (node (ref "U1") (pin "16") (pinfunction "PA6_16") (pintype "bidirectional"))
    )
    (net (code "34") (name "LED1") (class "Default")
      (node (ref "R110") (pin "1") (pinfunction "1_1") (pintype "passive"))
      (node (ref "U1") (pin "17") (pinfunction "PA7_17") (pintype "bidirectional"))
    )
    (net (code "35") (name "LED2") (class "Default")
      (node (ref "R111") (pin "1") (pinfunction "1_1") (pintype "passive"))
      (node (ref "U1") (pin "18") (pinfunction "PB0_18") (pintype "bidirectional"))
    )
    (net (code "36") (name "LED_CAN") (class "Default")
      (node (ref "R21") (pin "1") (pinfunction "1_1") (pintype "passive"))
      (node (ref "U1") (pin "3") (pinfunction "PC14-OSC32_IN_3") (pintype "bidirectional"))
    )
    (net (code "37") (name "Net-(D9-PadA)") (class "Default")
      (node (ref "D9") (pin "A") (pinfunction "A_A") (pintype "passive"))
      (node (ref "R109") (pin "2") (pinfunction "2_2") (pintype "passive"))
    )
    (net (code "38") (name "Net-(D10-PadA)") (class "Default")
      (node (ref "D10") (pin "A") (pinfunction "A_A") (pintype "passive"))
      (node (ref "R110") (pin "2") (pinfunction "2_2") (pintype "passive"))
    )
    (net (code "39") (name "Net-(D11-PadA)") (class "Default")
      (node (ref "D11") (pin "A") (pinfunction "A_A") (pintype "passive"))
      (node (ref "R111") (pin "2") (pinfunction "2_2") (pintype "passive"))
    )
    (net (code "40") (name "Net-(F1-Pad2)") (class "Default")
      (node (ref "F1") (pin "2") (pinfunction "2_2") (pintype "passive"))
      (node (ref "J1") (pin "4") (pinfunction "4_4") (pintype "input"))
      (node (ref "J1") (pin "5") (pinfunction "5_5") (pintype "input"))
      (node (ref "R20") (pin "1") (pinfunction "1_1") (pintype "passive"))
    )
    (net (code "41") (name "Net-(J1-A-G)") (class "Default")
      (node (ref "J1") (pin "GA") (pinfunction "A-G_GA") (pintype "passive"))
      (node (ref "R20") (pin "2") (pinfunction "2_2") (pintype "passive"))
    )
    (net (code "42") (name "Net-(J1-A-Y)") (class "Default")
      (node (ref "J1") (pin "YA") (pinfunction "A-Y_YA") (pintype "passive"))
      (node (ref "R21") (pin "2") (pinfunction "2_2") (pintype "passive"))
    )
    (net (code "43") (name "Net-(J6-Pad2)") (class "Default")
      (node (ref "J6") (pin "2") (pinfunction "2_2") (pintype "passive"))
      (node (ref "R12") (pin "2") (pinfunction "2_2") (pintype "passive"))
    )
    (net (code "44") (name "Net-(Q1-GATE)") (class "Default")
      (node (ref "Q1") (pin "4") (pinfunction "GATE_4") (pintype "passive"))
      (node (ref "R1") (pin "2") (pinfunction "2_2") (pintype "passive"))
    )
    (net (code "45") (name "Net-(Q2-GATE)") (class "Default")
      (node (ref "Q2") (pin "4") (pinfunction "GATE_4") (pintype "passive"))
      (node (ref "R3") (pin "2") (pinfunction "2_2") (pintype "passive"))
    )
    (net (code "46") (name "Net-(Q3-GATE)") (class "Default")
      (node (ref "Q3") (pin "4") (pinfunction "GATE_4") (pintype "passive"))
      (node (ref "R2") (pin "2") (pinfunction "2_2") (pintype "passive"))
    )
    (net (code "47") (name "Net-(Q4-GATE)") (class "Default")
      (node (ref "Q4") (pin "4") (pinfunction "GATE_4") (pintype "passive"))
      (node (ref "R4") (pin "2") (pinfunction "2_2") (pintype "passive"))
    )
    (net (code "48") (name "Net-(U1-OSC_IN)") (class "Default")
      (node (ref "U1") (pin "5") (pinfunction "OSC_IN_5") (pintype "input"))
      (node (ref "X1") (pin "1") (pinfunction "1_1") (pintype "passive"))
    )
    (net (code "49") (name "Net-(U1-OSC_OUT)") (class "Default")
      (node (ref "U1") (pin "6") (pinfunction "OSC_OUT_6") (pintype "output"))
      (node (ref "X1") (pin "3") (pinfunction "3_3") (pintype "passive"))
    )
    (net (code "50") (name "Net-(U2-RXD)") (class "Default")
      (node (ref "U2") (pin "4") (pinfunction "RXD_4") (pintype "output"))
      (node (ref "U3") (pin "6") (pinfunction "B2_6") (pintype "output"))
    )
    (net (code "51") (name "Net-(U2-TXD)") (class "Default")
      (node (ref "U2") (pin "1") (pinfunction "TXD_1") (pintype "input"))
      (node (ref "U3") (pin "7") (pinfunction "B1_7") (pintype "output"))
    )
    (net (code "52") (name "Net-(U4-AC1)") (class "Default")
      (node (ref "R28") (pin "1") (pinfunction "1_1") (pintype "passive"))
      (node (ref "U4") (pin "1") (pinfunction "AC1_1") (pintype "passive"))
    )
    (net (code "53") (name "Net-(U5-DRV_HI)") (class "Default")
      (node (ref "R1") (pin "1") (pinfunction "1_1") (pintype "passive"))
      (node (ref "R5") (pin "2") (pinfunction "2_2") (pintype "passive"))
      (node (ref "U5") (pin "7") (pinfunction "DRV_HI_7") (pintype "output"))
    )
    (net (code "54") (name "Net-(U5-DRV_LO)") (class "Default")
      (node (ref "R3") (pin "1") (pinfunction "1_1") (pintype "passive"))
      (node (ref "R7") (pin "2") (pinfunction "2_2") (pintype "passive"))
      (node (ref "U5") (pin "5") (pinfunction "DRV_LO_5") (pintype "output"))
    )
    (net (code "55") (name "Net-(U5-VBOOT)") (class "Default")
      (node (ref "C9") (pin "1") (pinfunction "1_1") (pintype "passive"))
      (node (ref "D1") (pin "C") (pinfunction "C_C") (pintype "passive"))
      (node (ref "U5") (pin "8") (pinfunction "VBOOT_8") (pintype "power_in"))
    )
    (net (code "56") (name "Net-(U6-DRV_HI)") (class "Default")
      (node (ref "R2") (pin "1") (pinfunction "1_1") (pintype "passive"))
      (node (ref "R6") (pin "2") (pinfunction "2_2") (pintype "passive"))
      (node (ref "U6") (pin "7") (pinfunction "DRV_HI_7") (pintype "output"))
    )
    (net (code "57") (name "Net-(U6-DRV_LO)") (class "Default")
      (node (ref "R4") (pin "1") (pinfunction "1_1") (pintype "passive"))
      (node (ref "R8") (pin "2") (pinfunction "2_2") (pintype "passive"))
      (node (ref "U6") (pin "5") (pinfunction "DRV_LO_5") (pintype "output"))
    )
    (net (code "58") (name "Net-(U6-VBOOT)") (class "Default")
      (node (ref "C10") (pin "1") (pinfunction "1_1") (pintype "passive"))
      (node (ref "D4") (pin "C") (pinfunction "C_C") (pintype "passive"))
      (node (ref "U6") (pin "8") (pinfunction "VBOOT_8") (pintype "power_in"))
    )
    (net (code "59") (name "Net-(U7-IN+)") (class "Default")
      (node (ref "C14") (pin "2") (pinfunction "2_2") (pintype "passive"))
      (node (ref "R10") (pin "2") (pinfunction "2_2") (pintype "passive"))
      (node (ref "U7") (pin "4") (pinfunction "IN+_4") (pintype "passive"))
    )
    (net (code "60") (name "Net-(U7-IN-)") (class "Default")
      (node (ref "C14") (pin "1") (pinfunction "1_1") (pintype "passive"))
      (node (ref "R11") (pin "2") (pinfunction "2_2") (pintype "passive"))
      (node (ref "U7") (pin "5") (pinfunction "IN-_5") (pintype "passive"))
    )
    (net (code "61") (name "Net-(U7-OUT)") (class "Default")
      (node (ref "R123") (pin "2") (pinfunction "2_2") (pintype "passive"))
      (node (ref "U7") (pin "6") (pinfunction "OUT_6") (pintype "passive"))
    )
    (net (code "62") (name "SWCLK") (class "Default")
      (node (ref "J4") (pin "4") (pinfunction "4_4") (pintype "passive"))
      (node (ref "U1") (pin "37") (pinfunction "PA14-JTCK-SWCLK_37") (pintype "bidirectional"))
    )
    (net (code "63") (name "SWDIO") (class "Default")
      (node (ref "J4") (pin "6") (pinfunction "6_6") (pintype "passive"))
      (node (ref "U1") (pin "34") (pinfunction "PA13-JTMS-SWDIO_34") (pintype "bidirectional"))
    )
    (net (code "64") (name "UART_RX") (class "Default")
      (node (ref "J4") (pin "1") (pinfunction "1_1") (pintype "passive"))
      (node (ref "U1") (pin "43") (pinfunction "PB7_43") (pintype "bidirectional"))
    )
    (net (code "65") (name "UART_TX") (class "Default")
      (node (ref "J4") (pin "3") (pinfunction "3_3") (pintype "passive"))
      (node (ref "U1") (pin "42") (pinfunction "PB6_42") (pintype "bidirectional"))
    )
    (net (code "66") (name "VCC") (class "Default")
      (node (ref "C1") (pin "+") (pinfunction "+_+") (pintype "passive"))
      (node (ref "C11") (pin "1") (pinfunction "1_1") (pintype "passive"))
      (node (ref "C12") (pin "1") (pinfunction "1_1") (pintype "passive"))
      (node (ref "C2") (pin "+") (pinfunction "+_+") (pintype "passive"))
      (node (ref "C3") (pin "1") (pinfunction "1_1") (pintype "passive"))
      (node (ref "C5") (pin "1") (pinfunction "1_1") (pintype "passive"))
      (node (ref "C6") (pin "1") (pinfunction "1_1") (pintype "passive"))
      (node (ref "Q1") (pin "5") (pinfunction "DRAIN_5") (pintype "passive"))
      (node (ref "Q3") (pin "5") (pinfunction "DRAIN_5") (pintype "passive"))
      (node (ref "R13") (pin "2") (pinfunction "2_2") (pintype "passive"))
      (node (ref "U8") (pin "1") (pinfunction "VI_1") (pintype "input"))
    )
    (net (code "67") (name "VCS") (class "Default")
      (node (ref "C11") (pin "2") (pinfunction "2_2") (pintype "passive"))
      (node (ref "C12") (pin "2") (pinfunction "2_2") (pintype "passive"))
      (node (ref "C13") (pin "2") (pinfunction "2_2") (pintype "passive"))
      (node (ref "C5") (pin "2") (pinfunction "2_2") (pintype "passive"))
      (node (ref "C6") (pin "2") (pinfunction "2_2") (pintype "passive"))
      (node (ref "Q2") (pin "1") (pinfunction "SOURCE_1") (pintype "passive"))
      (node (ref "Q2") (pin "2") (pinfunction "SOURCE_2") (pintype "passive"))
      (node (ref "Q2") (pin "3") (pinfunction "SOURCE_3") (pintype "passive"))
      (node (ref "Q4") (pin "1") (pinfunction "SOURCE_1") (pintype "passive"))
      (node (ref "Q4") (pin "2") (pinfunction "SOURCE_2") (pintype "passive"))
      (node (ref "Q4") (pin "3") (pinfunction "SOURCE_3") (pintype "passive"))
      (node (ref "R7") (pin "1") (pinfunction "1_1") (pintype "passive"))
      (node (ref "R8") (pin "1") (pinfunction "1_1") (pintype "passive"))
      (node (ref "R9") (pin "2$1") (pinfunction "2_2$1") (pintype "passive"))
      (node (ref "R9") (pin "2$2") (pinfunction "2_2$2") (pintype "passive"))
    )
    (net (code "68") (name "VCS_B_N") (class "Default")
      (node (ref "R11") (pin "1") (pinfunction "1_1") (pintype "passive"))
      (node (ref "R9") (pin "1S") (pinfunction "1S_1S") (pintype "passive"))
    )
    (net (code "69") (name "VCS_B_P") (class "Default")
      (node (ref "R10") (pin "1") (pinfunction "1_1") (pintype "passive"))
      (node (ref "R9") (pin "2S") (pinfunction "2S_2S") (pintype "passive"))
    )
    (net (code "70") (name "VSENSE") (class "Default")
      (node (ref "C17") (pin "2") (pinfunction "2_2") (pintype "passive"))
      (node (ref "R13") (pin "1") (pinfunction "1_1") (pintype "passive"))
      (node (ref "R14") (pin "2") (pinfunction "2_2") (pintype "passive"))
      (node (ref "U1") (pin "15") (pinfunction "PA5_15") (pintype "bidirectional"))
    )
    (net (code "71") (name "unconnected-(U1-PA10-Pad31)") (class "Default")
      (node (ref "U1") (pin "31") (pinfunction "PA10_31") (pintype "bidirectional"))
    )
    (net (code "72") (name "unconnected-(U1-PA11-Pad32)") (class "Default")
      (node (ref "U1") (pin "32") (pinfunction "PA11_32") (pintype "bidirectional"))
    )
    (net (code "73") (name "unconnected-(U1-PA12-Pad33)") (class "Default")
      (node (ref "U1") (pin "33") (pinfunction "PA12_33") (pintype "bidirectional"))
    )
    (net (code "74") (name "unconnected-(U1-PA15-JTDI-Pad38)") (class "Default")
      (node (ref "U1") (pin "38") (pinfunction "PA15-JTDI_38") (pintype "bidirectional"))
    )
    (net (code "75") (name "unconnected-(U1-PB3-JTDO-Pad39)") (class "Default")
      (node (ref "U1") (pin "39") (pinfunction "PB3-JTDO_39") (pintype "bidirectional"))
    )
    (net (code "76") (name "unconnected-(U1-PB4-JNTRST-Pad40)") (class "Default")
      (node (ref "U1") (pin "40") (pinfunction "PB4-JNTRST_40") (pintype "bidirectional"))
    )
    (net (code "77") (name "unconnected-(U1-PB5-Pad41)") (class "Default")
      (node (ref "U1") (pin "41") (pinfunction "PB5_41") (pintype "bidirectional"))
    )
    (net (code "78") (name "unconnected-(U1-PB15-Pad28)") (class "Default")
      (node (ref "U1") (pin "28") (pinfunction "PB15_28") (pintype "bidirectional"))
    )
    (net (code "79") (name "unconnected-(U1-PC15-OSC32_OUT-Pad4)") (class "Default")
      (node (ref "U1") (pin "4") (pinfunction "PC15-OSC32_OUT_4") (pintype "bidirectional"))
    )
    (net (code "80") (name "unconnected-(U1-VBAT-Pad1)") (class "Default")
      (node (ref "U1") (pin "1") (pinfunction "VBAT_1") (pintype "passive"))
    )
    (net (code "81") (name "~{EMS_ISO}") (class "Default")
      (node (ref "J1") (pin "6") (pinfunction "6_6") (pintype "input"))
      (node (ref "R28") (pin "2") (pinfunction "2_2") (pintype "passive"))
    )
    (net (code "82") (name "~{EMS}") (class "Default")
      (node (ref "R30") (pin "2") (pinfunction "2_2") (pintype "passive"))
      (node (ref "U1") (pin "2") (pinfunction "PC13-TAMPER-RTC_2") (pintype "bidirectional"))
      (node (ref "U12") (pin "1") (pinfunction "I0_1") (pintype "input"))
      (node (ref "U13") (pin "1") (pinfunction "I0_1") (pintype "input"))
      (node (ref "U14") (pin "1") (pinfunction "I0_1") (pintype "input"))
      (node (ref "U15") (pin "1") (pinfunction "I0_1") (pintype "input"))
      (node (ref "U4") (pin "3") (pinfunction "E_3") (pintype "passive"))
    )
    (net (code "83") (name "~{RESET}") (class "Default")
      (node (ref "C22") (pin "2") (pinfunction "2_2") (pintype "passive"))
      (node (ref "S1") (pin "P$2") (pinfunction "2_P$2") (pintype "bidirectional"))
      (node (ref "U1") (pin "7") (pinfunction "NRST_7") (pintype "bidirectional"))
    )
  )
)
